# untitled.net
KiCad netlist of a schematic drawn in EAGLE
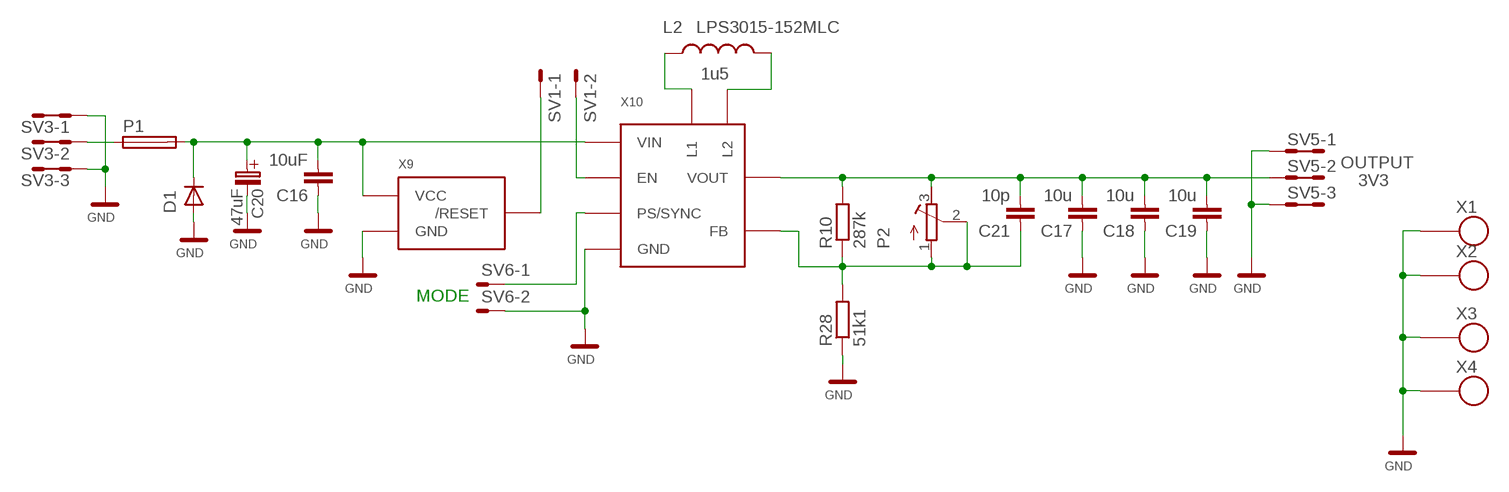
[diagram p0: schematic, sheet 1]

(export (version "E")
  (design (tool "Eeschema 10.0.6"))
  (components
    (comp (ref "C16")
      (value "10uF")
      (footprint "eagle-import:C0805")
      (libsource (lib "eagle-import") (part "C0805"))
    )
    (comp (ref "C17")
      (value "10u")
      (footprint "eagle-import:C0805")
      (libsource (lib "eagle-import") (part "C0805"))
    )
    (comp (ref "C18")
      (value "10u")
      (footprint "eagle-import:C0805")
      (libsource (lib "eagle-import") (part "C0805"))
    )
    (comp (ref "C19")
      (value "10u")
      (footprint "eagle-import:C0805")
      (libsource (lib "eagle-import") (part "C0805"))
    )
    (comp (ref "C20") (value "47uF") (footprint "eagle-import:B") (libsource (lib "eagle-import") (part "B")))
    (comp (ref "C21")
      (value "10p")
      (footprint "eagle-import:0603")
      (libsource (lib "eagle-import") (part "C0603"))
    )
    (comp (ref "D1")
      (value "D-OB.SMA")
      (footprint "eagle-import:SMA")
      (libsource (lib "eagle-import") (part "D-OB.SMA"))
    )
    (comp (ref "L2")
      (value "LPS3015-152MLC")
      (footprint "eagle-import:LPS3015")
      (libsource (lib "eagle-import") (part "LPS3015"))
    )
    (comp (ref "P1")
      (value "POJISTKA_1812")
      (footprint "eagle-import:1812")
      (libsource (lib "eagle-import") (part "POJISTKA_1812"))
    )
    (comp (ref "P2")
      (value "TRIM_CA9MTV10")
      (footprint "eagle-import:TRIM_CA9MTV10")
      (libsource (lib "eagle-import") (part "TRIM_CA9MTV10"))
    )
    (comp (ref "R10")
      (value "287k")
      (footprint "eagle-import:0603")
      (libsource (lib "eagle-import") (part "R0603"))
    )
    (comp (ref "R28")
      (value "51k1")
      (footprint "eagle-import:0603")
      (libsource (lib "eagle-import") (part "R0603"))
    )
    (comp (ref "SV1")
      (value "MA02-1")
      (footprint "eagle-import:MA02-1")
      (libsource (lib "eagle-import") (part "MA02-1"))
    )
    (comp (ref "SV3")
      (value "MA03-2")
      (footprint "eagle-import:MA03-2")
      (libsource (lib "eagle-import") (part "MA03-2"))
    )
    (comp (ref "SV5")
      (value "MA03-2")
      (footprint "eagle-import:MA03-2")
      (libsource (lib "eagle-import") (part "MA03-2"))
    )
    (comp (ref "SV6")
      (value "MA02-1")
      (footprint "eagle-import:MA02-1")
      (libsource (lib "eagle-import") (part "MA02-1"))
    )
    (comp (ref "X1")
      (value "SROUB3M")
      (footprint "eagle-import:SROUB3M")
      (libsource (lib "eagle-import") (part "SROUB3M"))
    )
    (comp (ref "X2")
      (value "SROUB3M")
      (footprint "eagle-import:SROUB3M")
      (libsource (lib "eagle-import") (part "SROUB3M"))
    )
    (comp (ref "X3")
      (value "SROUB3M")
      (footprint "eagle-import:SROUB3M")
      (libsource (lib "eagle-import") (part "SROUB3M"))
    )
    (comp (ref "X4")
      (value "SROUB3M")
      (footprint "eagle-import:SROUB3M")
      (libsource (lib "eagle-import") (part "SROUB3M"))
    )
    (comp (ref "X9")
      (value "APX809-26SA")
      (footprint "eagle-import:SOT23")
      (libsource (lib "eagle-import") (part "APX809-26SA"))
    )
    (comp (ref "X10")
      (value "TPS63036")
      (footprint "eagle-import:DSBGA8")
      (libsource (lib "eagle-import") (part "TPS63036"))
    )
  )
  (nets
    (net (code "1") (name "GND") (class "Default")
      (node (ref "C16") (pin "1") (pinfunction "1_1") (pintype "passive"))
      (node (ref "C17") (pin "1") (pinfunction "1_1") (pintype "passive"))
      (node (ref "C18") (pin "1") (pinfunction "1_1") (pintype "passive"))
      (node (ref "C19") (pin "1") (pinfunction "1_1") (pintype "passive"))
      (node (ref "C20") (pin "-") (pinfunction "C_EL-_-") (pintype "passive"))
      (node (ref "D1") (pin "A") (pinfunction "A_A") (pintype "passive"))
      (node (ref "R28") (pin "1") (pinfunction "1_1") (pintype "passive"))
      (node (ref "SV3") (pin "1") (pinfunction "K_1") (pintype "passive"))
      (node (ref "SV3") (pin "2") (pinfunction "K_2") (pintype "passive"))
      (node (ref "SV3") (pin "5") (pinfunction "K_5") (pintype "passive"))
      (node (ref "SV3") (pin "6") (pinfunction "K_6") (pintype "passive"))
      (node (ref "SV5") (pin "1") (pinfunction "K_1") (pintype "passive"))
      (node (ref "SV5") (pin "2") (pinfunction "K_2") (pintype "passive"))
      (node (ref "SV5") (pin "5") (pinfunction "K_5") (pintype "passive"))
      (node (ref "SV5") (pin "6") (pinfunction "K_6") (pintype "passive"))
      (node (ref "SV6") (pin "2") (pinfunction "P$1_2") (pintype "passive"))
      (node (ref "X1") (pin "P$1") (pinfunction "P$1_P$1") (pintype "bidirectional"))
      (node (ref "X10") (pin "C2") (pinfunction "GND_C2") (pintype "passive"))
      (node (ref "X2") (pin "P$1") (pinfunction "P$1_P$1") (pintype "bidirectional"))
      (node (ref "X3") (pin "P$1") (pinfunction "P$1_P$1") (pintype "bidirectional"))
      (node (ref "X4") (pin "P$1") (pinfunction "P$1_P$1") (pintype "bidirectional"))
      (node (ref "X9") (pin "1") (pinfunction "GND_1") (pintype "passive"))
    )
    (net (code "2") (name "Net-(C20-C_EL+)") (class "Default")
      (node (ref "C16") (pin "2") (pinfunction "2_2") (pintype "passive"))
      (node (ref "C20") (pin "+") (pinfunction "C_EL+_+") (pintype "passive"))
      (node (ref "D1") (pin "K") (pinfunction "C_K") (pintype "passive"))
      (node (ref "P1") (pin "2") (pinfunction "2_2") (pintype "passive"))
      (node (ref "X10") (pin "A1") (pinfunction "VIN_A1") (pintype "input"))
      (node (ref "X9") (pin "3") (pinfunction "VCC_3") (pintype "input"))
    )
    (net (code "3") (name "Net-(P1-Pad1)") (class "Default")
      (node (ref "P1") (pin "1") (pinfunction "1_1") (pintype "passive"))
      (node (ref "SV3") (pin "3") (pinfunction "K_3") (pintype "passive"))
      (node (ref "SV3") (pin "4") (pinfunction "K_4") (pintype "passive"))
    )
    (net (code "4") (name "Net-(SV1A-P$1)") (class "Default")
      (node (ref "SV1") (pin "1") (pinfunction "P$1_1") (pintype "passive"))
      (node (ref "X9") (pin "2") (pinfunction "/RESET_2") (pintype "passive"))
    )
    (net (code "5") (name "Net-(SV1B-P$1)") (class "Default")
      (node (ref "SV1") (pin "2") (pinfunction "P$1_2") (pintype "passive"))
      (node (ref "X10") (pin "A2") (pinfunction "EN_A2") (pintype "input"))
    )
    (net (code "6") (name "Net-(SV6A-P$1)") (class "Default")
      (node (ref "SV6") (pin "1") (pinfunction "P$1_1") (pintype "passive"))
      (node (ref "X10") (pin "B2") (pinfunction "PS/SYNC_B2") (pintype "input"))
    )
    (net (code "7") (name "Net-(X10-FB)") (class "Default")
      (node (ref "C21") (pin "1") (pinfunction "1_1") (pintype "passive"))
      (node (ref "P2") (pin "1") (pinfunction "1_1") (pintype "passive"))
      (node (ref "P2") (pin "2") (pinfunction "2_2") (pintype "passive"))
      (node (ref "R10") (pin "1") (pinfunction "1_1") (pintype "passive"))
      (node (ref "R28") (pin "2") (pinfunction "2_2") (pintype "passive"))
      (node (ref "X10") (pin "D2") (pinfunction "FB_D2") (pintype "input"))
    )
    (net (code "8") (name "Net-(X10-L1)") (class "Default")
      (node (ref "L2") (pin "1-1") (pinfunction "1_1-1") (pintype "passive"))
      (node (ref "L2") (pin "1-2") (pinfunction "1_1-2") (pintype "passive"))
      (node (ref "L2") (pin "1-3") (pinfunction "1_1-3") (pintype "passive"))
      (node (ref "X10") (pin "B1") (pinfunction "L1_B1") (pintype "passive"))
    )
    (net (code "9") (name "Net-(X10-L2)") (class "Default")
      (node (ref "L2") (pin "2-1") (pinfunction "2_2-1") (pintype "passive"))
      (node (ref "L2") (pin "2-2") (pinfunction "2_2-2") (pintype "passive"))
      (node (ref "L2") (pin "2-3") (pinfunction "2_2-3") (pintype "passive"))
      (node (ref "X10") (pin "C1") (pinfunction "L2_C1") (pintype "passive"))
    )
    (net (code "10") (name "Net-(X10-VOUT)") (class "Default")
      (node (ref "C17") (pin "2") (pinfunction "2_2") (pintype "passive"))
      (node (ref "C18") (pin "2") (pinfunction "2_2") (pintype "passive"))
      (node (ref "C19") (pin "2") (pinfunction "2_2") (pintype "passive"))
      (node (ref "C21") (pin "2") (pinfunction "2_2") (pintype "passive"))
      (node (ref "P2") (pin "3") (pinfunction "3_3") (pintype "passive"))
      (node (ref "R10") (pin "2") (pinfunction "2_2") (pintype "passive"))
      (node (ref "SV5") (pin "3") (pinfunction "K_3") (pintype "passive"))
      (node (ref "SV5") (pin "4") (pinfunction "K_4") (pintype "passive"))
      (node (ref "X10") (pin "D1") (pinfunction "VOUT_D1") (pintype "output"))
    )
  )
)
